# schematic_easyeda.net
KiCad netlist of a schematic drawn in EasyEDA
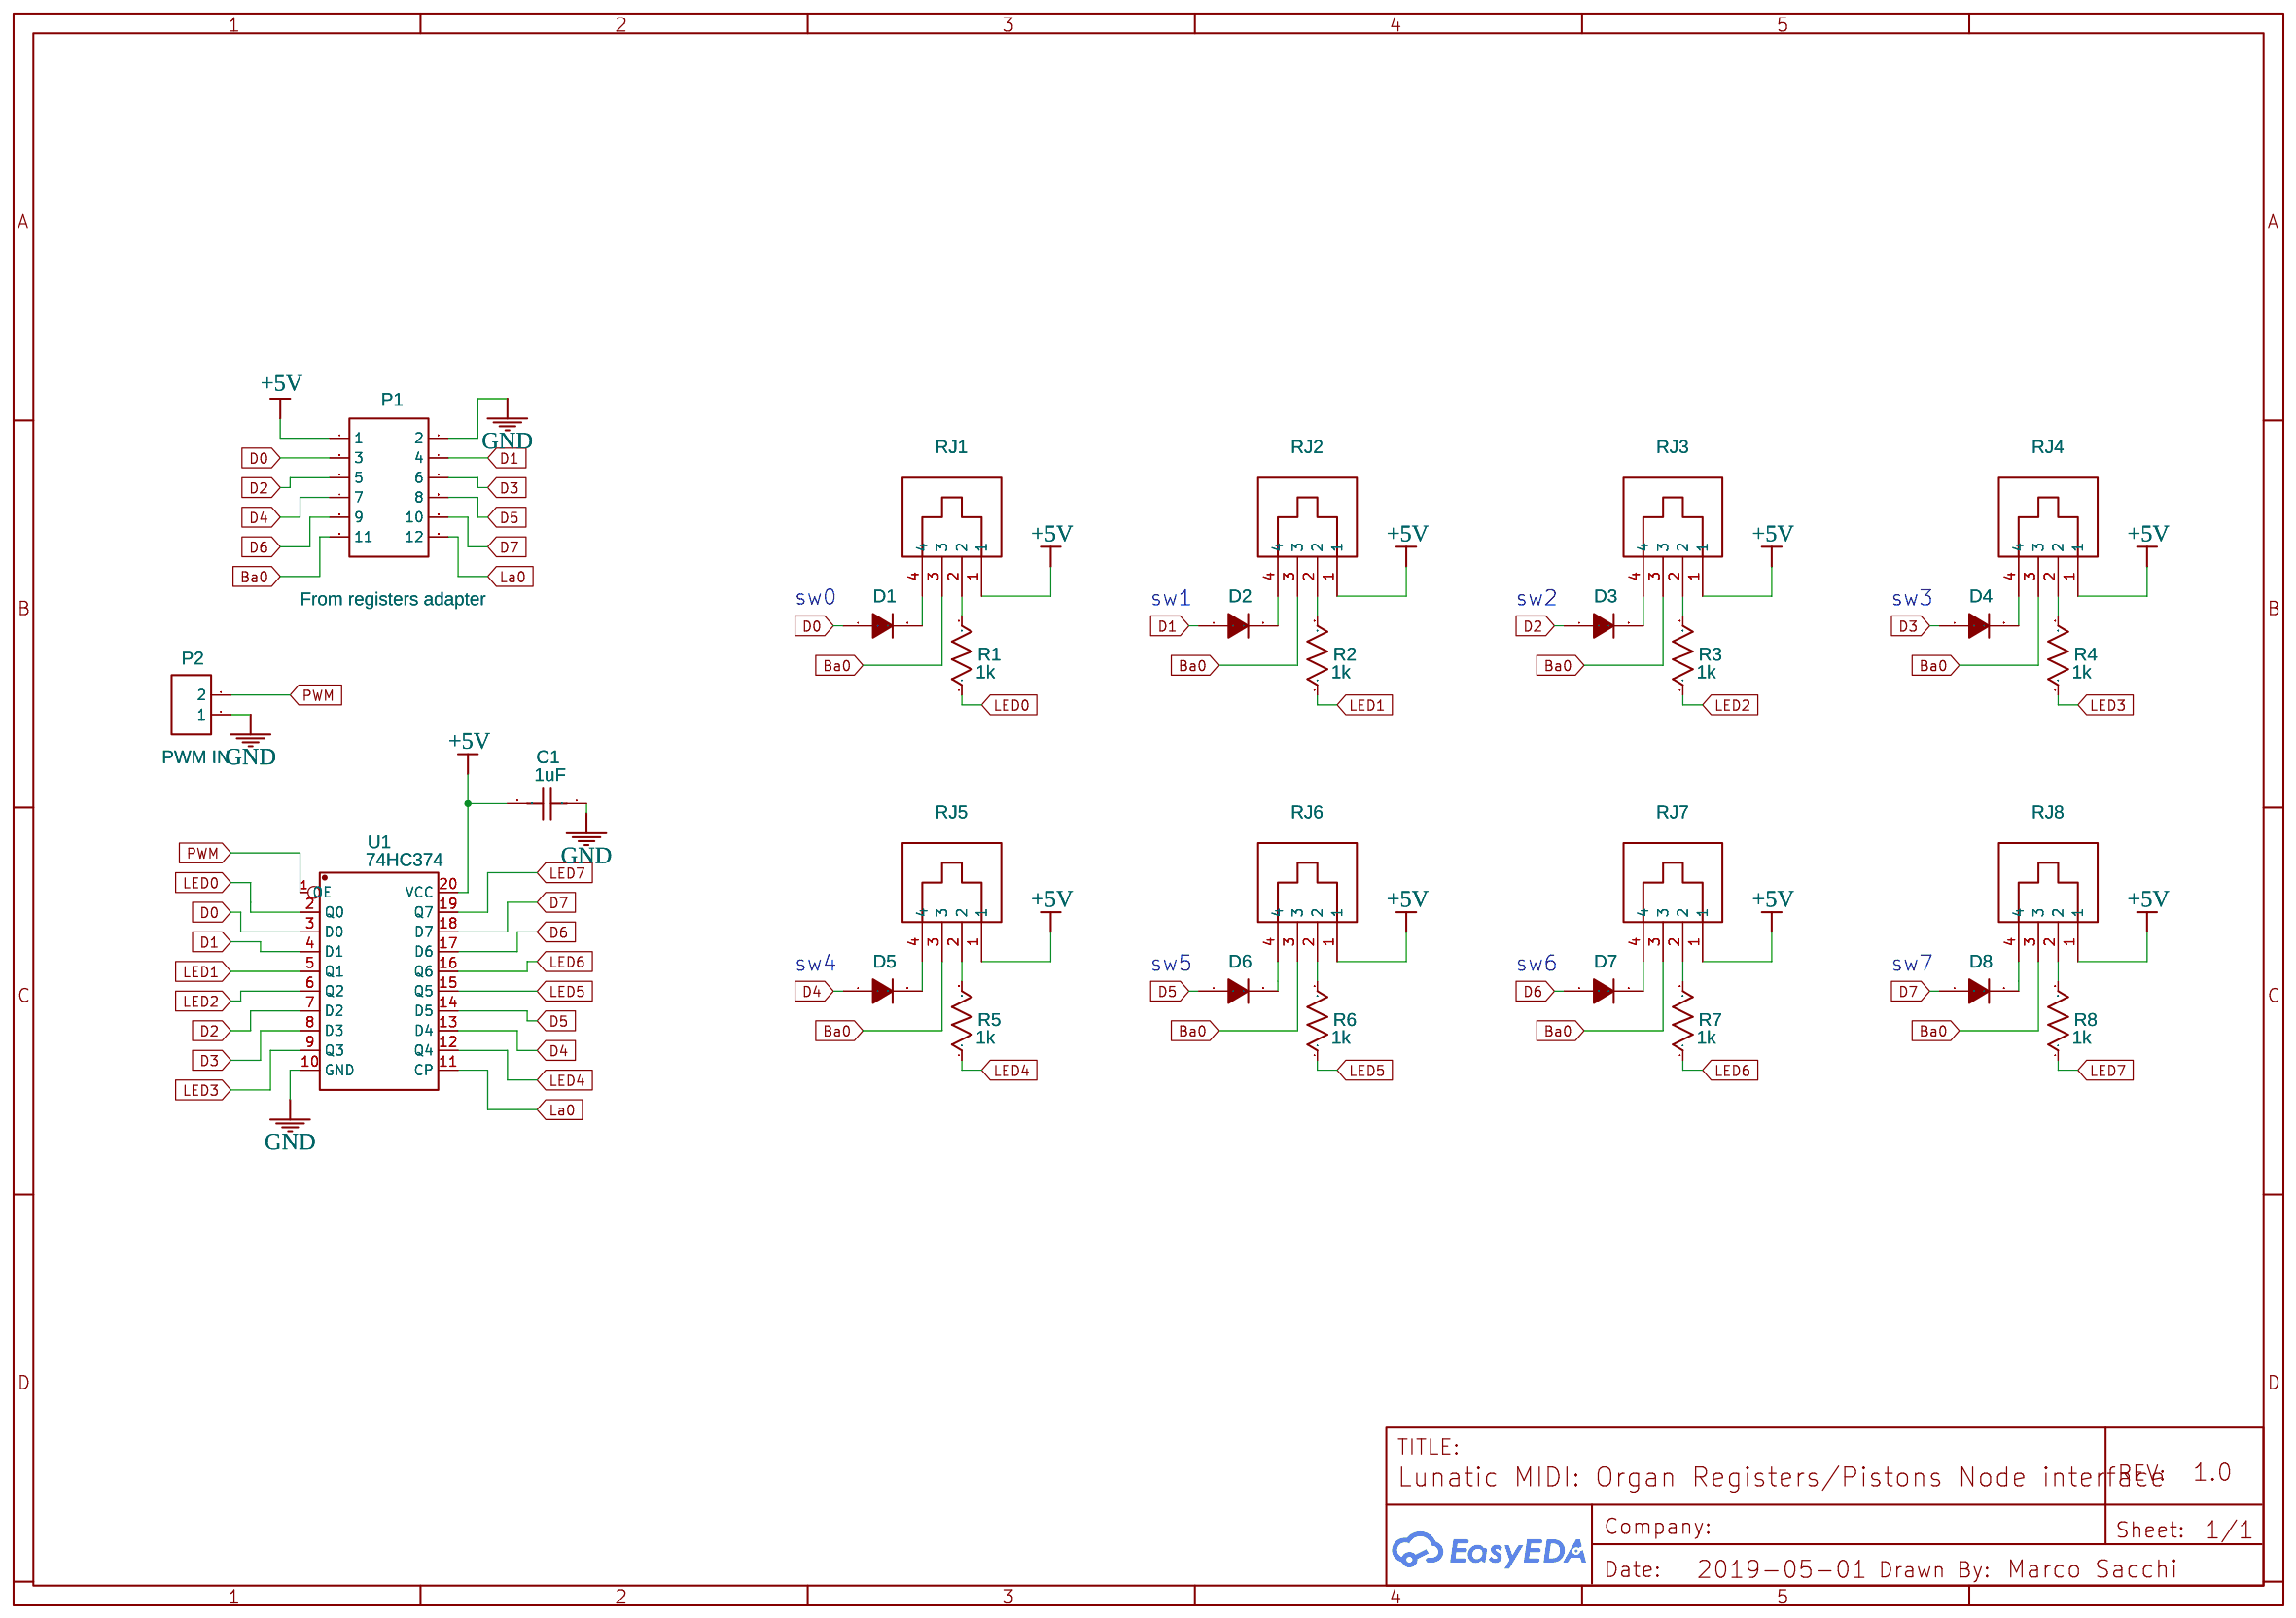
[diagram p0: schematic sheet]

(export (version "E")
  (design (tool "Eeschema 10.0.6"))
  (components
    (comp (ref "C1")
      (value "1uF")
      (fields (field (name "BOM_Manufacturer Part") "?"))
      (libsource (lib "") (part "Cap_RAD-0.1_US"))
    )
    (comp (ref "D1")
      (value "1N4148")
      (fields (field (name "BOM_Supplier Part") "C85057"))
      (libsource (lib "") (part "Unknown_440_310"))
    )
    (comp (ref "D2")
      (value "1N4148")
      (fields (field (name "BOM_Supplier Part") "C85057"))
      (libsource (lib "") (part "Unknown_620_310"))
    )
    (comp (ref "D3")
      (value "1N4148")
      (fields (field (name "BOM_Supplier Part") "C85057"))
      (libsource (lib "") (part "Unknown_805_310"))
    )
    (comp (ref "D4")
      (value "1N4148")
      (fields (field (name "BOM_Supplier Part") "C85057"))
      (libsource (lib "") (part "Unknown_995_310"))
    )
    (comp (ref "D5")
      (value "1N4148")
      (fields (field (name "BOM_Supplier Part") "C85057"))
      (libsource (lib "") (part "Unknown_440_495"))
    )
    (comp (ref "D6")
      (value "1N4148")
      (fields (field (name "BOM_Supplier Part") "C85057"))
      (libsource (lib "") (part "Unknown_620_495"))
    )
    (comp (ref "D7")
      (value "1N4148")
      (fields (field (name "BOM_Supplier Part") "C85057"))
      (libsource (lib "") (part "Unknown_805_495"))
    )
    (comp (ref "D8")
      (value "1N4148")
      (fields (field (name "BOM_Supplier Part") "C85057"))
      (libsource (lib "") (part "Unknown_995_495"))
    )
    (comp (ref "P1")
      (value "From registers adapter")
      (fields (field (name "BOM_Manufacturer Part") "?") (field (name "BOM_Supplier Part") "C66689"))
      (libsource (lib "") (part "Unknown_190_240"))
    )
    (comp (ref "P2")
      (value "PWM IN")
      (fields
        (field (name "BOM_Manufacturer Part") "2.54-1*2PFemale")
        (field (name "BOM_Supplier Part") "C49661")
      )
      (libsource (lib "") (part "Unknown_95_350"))
    )
    (comp (ref "R1")
      (value "1k")
      (fields (field (name "BOM_Manufacturer Part") "?"))
      (libsource (lib "") (part "Res_AXIAL-0.3(1/8W)_US"))
    )
    (comp (ref "R2")
      (value "1k")
      (fields (field (name "BOM_Manufacturer Part") "?"))
      (libsource (lib "") (part "Res_AXIAL-0.3(1/8W)_US"))
    )
    (comp (ref "R3")
      (value "1k")
      (fields (field (name "BOM_Manufacturer Part") "?"))
      (libsource (lib "") (part "Res_AXIAL-0.3(1/8W)_US"))
    )
    (comp (ref "R4")
      (value "1k")
      (fields (field (name "BOM_Manufacturer Part") "?"))
      (libsource (lib "") (part "Res_AXIAL-0.3(1/8W)_US"))
    )
    (comp (ref "R5")
      (value "1k")
      (fields (field (name "BOM_Manufacturer Part") "?"))
      (libsource (lib "") (part "Res_AXIAL-0.3(1/8W)_US"))
    )
    (comp (ref "R6")
      (value "1k")
      (fields (field (name "BOM_Manufacturer Part") "?"))
      (libsource (lib "") (part "Res_AXIAL-0.3(1/8W)_US"))
    )
    (comp (ref "R7")
      (value "1k")
      (fields (field (name "BOM_Manufacturer Part") "?"))
      (libsource (lib "") (part "Res_AXIAL-0.3(1/8W)_US"))
    )
    (comp (ref "R8")
      (value "1k")
      (fields (field (name "BOM_Manufacturer Part") "?"))
      (libsource (lib "") (part "Res_AXIAL-0.3(1/8W)_US"))
    )
    (comp (ref "RJ1")
      (value "RJ22-4P4C-90")
      (fields
        (field (name "BOM_Manufacturer Part") "1-1705949-1")
        (field (name "BOM_Supplier Part") "615-4232")
      )
      (libsource (lib "") (part "Unknown_475_265"))
    )
    (comp (ref "RJ2")
      (value "RJ22-4P4C-90")
      (fields
        (field (name "BOM_Manufacturer Part") "1-1705949-1")
        (field (name "BOM_Supplier Part") "615-4232")
      )
      (libsource (lib "") (part "Unknown_655_265"))
    )
    (comp (ref "RJ3")
      (value "RJ22-4P4C-90")
      (fields
        (field (name "BOM_Manufacturer Part") "1-1705949-1")
        (field (name "BOM_Supplier Part") "615-4232")
      )
      (libsource (lib "") (part "Unknown_840_265"))
    )
    (comp (ref "RJ4")
      (value "RJ22-4P4C-90")
      (fields
        (field (name "BOM_Manufacturer Part") "1-1705949-1")
        (field (name "BOM_Supplier Part") "615-4232")
      )
      (libsource (lib "") (part "Unknown_1030_265"))
    )
    (comp (ref "RJ5")
      (value "RJ22-4P4C-90")
      (fields
        (field (name "BOM_Manufacturer Part") "1-1705949-1")
        (field (name "BOM_Supplier Part") "615-4232")
      )
      (libsource (lib "") (part "Unknown_475_450"))
    )
    (comp (ref "RJ6")
      (value "RJ22-4P4C-90")
      (fields
        (field (name "BOM_Manufacturer Part") "1-1705949-1")
        (field (name "BOM_Supplier Part") "615-4232")
      )
      (libsource (lib "") (part "Unknown_655_450"))
    )
    (comp (ref "RJ7")
      (value "RJ22-4P4C-90")
      (fields
        (field (name "BOM_Manufacturer Part") "1-1705949-1")
        (field (name "BOM_Supplier Part") "615-4232")
      )
      (libsource (lib "") (part "Unknown_840_450"))
    )
    (comp (ref "RJ8")
      (value "RJ22-4P4C-90")
      (fields
        (field (name "BOM_Manufacturer Part") "1-1705949-1")
        (field (name "BOM_Supplier Part") "615-4232")
      )
      (libsource (lib "") (part "Unknown_1030_450"))
    )
    (comp (ref "U1")
      (value "74HC374")
      (fields (field (name "BOM_Supplier Part") "CD54"))
      (libsource (lib "") (part "Unknown_185_490"))
    )
  )
  (nets
    (net (code "1") (name "+5V") (class "Default")
      (node (ref "C1") (pin "2") (pinfunction "2_2") (pintype "unspecified"))
      (node (ref "P1") (pin "1") (pinfunction "1_1") (pintype "input"))
      (node (ref "RJ1") (pin "1") (pinfunction "1_1") (pintype "unspecified"))
      (node (ref "RJ2") (pin "1") (pinfunction "1_1") (pintype "unspecified"))
      (node (ref "RJ3") (pin "1") (pinfunction "1_1") (pintype "unspecified"))
      (node (ref "RJ4") (pin "1") (pinfunction "1_1") (pintype "unspecified"))
      (node (ref "RJ5") (pin "1") (pinfunction "1_1") (pintype "unspecified"))
      (node (ref "RJ6") (pin "1") (pinfunction "1_1") (pintype "unspecified"))
      (node (ref "RJ7") (pin "1") (pinfunction "1_1") (pintype "unspecified"))
      (node (ref "RJ8") (pin "1") (pinfunction "1_1") (pintype "unspecified"))
      (node (ref "U1") (pin "20") (pinfunction "VCC_20") (pintype "unspecified"))
    )
    (net (code "2") (name "Ba0") (class "Default")
      (node (ref "P1") (pin "11") (pinfunction "11_11") (pintype "input"))
      (node (ref "RJ1") (pin "3") (pinfunction "3_3") (pintype "unspecified"))
      (node (ref "RJ2") (pin "3") (pinfunction "3_3") (pintype "unspecified"))
      (node (ref "RJ3") (pin "3") (pinfunction "3_3") (pintype "unspecified"))
      (node (ref "RJ4") (pin "3") (pinfunction "3_3") (pintype "unspecified"))
      (node (ref "RJ5") (pin "3") (pinfunction "3_3") (pintype "unspecified"))
      (node (ref "RJ6") (pin "3") (pinfunction "3_3") (pintype "unspecified"))
      (node (ref "RJ7") (pin "3") (pinfunction "3_3") (pintype "unspecified"))
      (node (ref "RJ8") (pin "3") (pinfunction "3_3") (pintype "unspecified"))
    )
    (net (code "3") (name "D0") (class "Default")
      (node (ref "D1") (pin "1") (pinfunction "A_1") (pintype "unspecified"))
      (node (ref "P1") (pin "3") (pinfunction "3_3") (pintype "input"))
      (node (ref "U1") (pin "3") (pinfunction "D0_3") (pintype "unspecified"))
    )
    (net (code "4") (name "D1") (class "Default")
      (node (ref "D2") (pin "1") (pinfunction "A_1") (pintype "unspecified"))
      (node (ref "P1") (pin "4") (pinfunction "4_4") (pintype "input"))
      (node (ref "U1") (pin "4") (pinfunction "D1_4") (pintype "unspecified"))
    )
    (net (code "5") (name "D2") (class "Default")
      (node (ref "D3") (pin "1") (pinfunction "A_1") (pintype "unspecified"))
      (node (ref "P1") (pin "5") (pinfunction "5_5") (pintype "input"))
      (node (ref "U1") (pin "7") (pinfunction "D2_7") (pintype "unspecified"))
    )
    (net (code "6") (name "D3") (class "Default")
      (node (ref "D4") (pin "1") (pinfunction "A_1") (pintype "unspecified"))
      (node (ref "P1") (pin "6") (pinfunction "6_6") (pintype "input"))
      (node (ref "U1") (pin "8") (pinfunction "D3_8") (pintype "unspecified"))
    )
    (net (code "7") (name "D4") (class "Default")
      (node (ref "D5") (pin "1") (pinfunction "A_1") (pintype "unspecified"))
      (node (ref "P1") (pin "7") (pinfunction "7_7") (pintype "input"))
      (node (ref "U1") (pin "13") (pinfunction "D4_13") (pintype "unspecified"))
    )
    (net (code "8") (name "D5") (class "Default")
      (node (ref "D6") (pin "1") (pinfunction "A_1") (pintype "unspecified"))
      (node (ref "P1") (pin "8") (pinfunction "8_8") (pintype "input"))
      (node (ref "U1") (pin "14") (pinfunction "D5_14") (pintype "unspecified"))
    )
    (net (code "9") (name "D6") (class "Default")
      (node (ref "D7") (pin "1") (pinfunction "A_1") (pintype "unspecified"))
      (node (ref "P1") (pin "9") (pinfunction "9_9") (pintype "input"))
      (node (ref "U1") (pin "17") (pinfunction "D6_17") (pintype "unspecified"))
    )
    (net (code "10") (name "D7") (class "Default")
      (node (ref "D8") (pin "1") (pinfunction "A_1") (pintype "unspecified"))
      (node (ref "P1") (pin "10") (pinfunction "10_10") (pintype "input"))
      (node (ref "U1") (pin "18") (pinfunction "D7_18") (pintype "unspecified"))
    )
    (net (code "11") (name "GND") (class "Default")
      (node (ref "C1") (pin "1") (pinfunction "1_1") (pintype "unspecified"))
      (node (ref "P1") (pin "2") (pinfunction "2_2") (pintype "input"))
      (node (ref "P2") (pin "1") (pinfunction "1_1") (pintype "input"))
      (node (ref "U1") (pin "10") (pinfunction "GND_10") (pintype "unspecified"))
    )
    (net (code "12") (name "LED0") (class "Default")
      (node (ref "R1") (pin "1") (pinfunction "1_1") (pintype "unspecified"))
      (node (ref "U1") (pin "2") (pinfunction "Q0_2") (pintype "unspecified"))
    )
    (net (code "13") (name "LED1") (class "Default")
      (node (ref "R2") (pin "1") (pinfunction "1_1") (pintype "unspecified"))
      (node (ref "U1") (pin "5") (pinfunction "Q1_5") (pintype "unspecified"))
    )
    (net (code "14") (name "LED2") (class "Default")
      (node (ref "R3") (pin "1") (pinfunction "1_1") (pintype "unspecified"))
      (node (ref "U1") (pin "6") (pinfunction "Q2_6") (pintype "unspecified"))
    )
    (net (code "15") (name "LED3") (class "Default")
      (node (ref "R4") (pin "1") (pinfunction "1_1") (pintype "unspecified"))
      (node (ref "U1") (pin "9") (pinfunction "Q3_9") (pintype "unspecified"))
    )
    (net (code "16") (name "LED4") (class "Default")
      (node (ref "R5") (pin "1") (pinfunction "1_1") (pintype "unspecified"))
      (node (ref "U1") (pin "12") (pinfunction "Q4_12") (pintype "unspecified"))
    )
    (net (code "17") (name "LED5") (class "Default")
      (node (ref "R6") (pin "1") (pinfunction "1_1") (pintype "unspecified"))
      (node (ref "U1") (pin "15") (pinfunction "Q5_15") (pintype "unspecified"))
    )
    (net (code "18") (name "LED6") (class "Default")
      (node (ref "R7") (pin "1") (pinfunction "1_1") (pintype "unspecified"))
      (node (ref "U1") (pin "16") (pinfunction "Q6_16") (pintype "unspecified"))
    )
    (net (code "19") (name "LED7") (class "Default")
      (node (ref "R8") (pin "1") (pinfunction "1_1") (pintype "unspecified"))
      (node (ref "U1") (pin "19") (pinfunction "Q7_19") (pintype "unspecified"))
    )
    (net (code "20") (name "La0") (class "Default")
      (node (ref "P1") (pin "12") (pinfunction "12_12") (pintype "input"))
      (node (ref "U1") (pin "11") (pinfunction "CP_11") (pintype "unspecified"))
    )
    (net (code "21") (name "Net-(D1-K)") (class "Default")
      (node (ref "D1") (pin "2") (pinfunction "K_2") (pintype "unspecified"))
      (node (ref "RJ1") (pin "4") (pinfunction "4_4") (pintype "unspecified"))
    )
    (net (code "22") (name "Net-(D2-K)") (class "Default")
      (node (ref "D2") (pin "2") (pinfunction "K_2") (pintype "unspecified"))
      (node (ref "RJ2") (pin "4") (pinfunction "4_4") (pintype "unspecified"))
    )
    (net (code "23") (name "Net-(D3-K)") (class "Default")
      (node (ref "D3") (pin "2") (pinfunction "K_2") (pintype "unspecified"))
      (node (ref "RJ3") (pin "4") (pinfunction "4_4") (pintype "unspecified"))
    )
    (net (code "24") (name "Net-(D4-K)") (class "Default")
      (node (ref "D4") (pin "2") (pinfunction "K_2") (pintype "unspecified"))
      (node (ref "RJ4") (pin "4") (pinfunction "4_4") (pintype "unspecified"))
    )
    (net (code "25") (name "Net-(D5-K)") (class "Default")
      (node (ref "D5") (pin "2") (pinfunction "K_2") (pintype "unspecified"))
      (node (ref "RJ5") (pin "4") (pinfunction "4_4") (pintype "unspecified"))
    )
    (net (code "26") (name "Net-(D6-K)") (class "Default")
      (node (ref "D6") (pin "2") (pinfunction "K_2") (pintype "unspecified"))
      (node (ref "RJ6") (pin "4") (pinfunction "4_4") (pintype "unspecified"))
    )
    (net (code "27") (name "Net-(D7-K)") (class "Default")
      (node (ref "D7") (pin "2") (pinfunction "K_2") (pintype "unspecified"))
      (node (ref "RJ7") (pin "4") (pinfunction "4_4") (pintype "unspecified"))
    )
    (net (code "28") (name "Net-(D8-K)") (class "Default")
      (node (ref "D8") (pin "2") (pinfunction "K_2") (pintype "unspecified"))
      (node (ref "RJ8") (pin "4") (pinfunction "4_4") (pintype "unspecified"))
    )
    (net (code "29") (name "Net-(R1-Pad2)") (class "Default")
      (node (ref "R1") (pin "2") (pinfunction "2_2") (pintype "unspecified"))
      (node (ref "RJ1") (pin "2") (pinfunction "2_2") (pintype "unspecified"))
    )
    (net (code "30") (name "Net-(R2-Pad2)") (class "Default")
      (node (ref "R2") (pin "2") (pinfunction "2_2") (pintype "unspecified"))
      (node (ref "RJ2") (pin "2") (pinfunction "2_2") (pintype "unspecified"))
    )
    (net (code "31") (name "Net-(R3-Pad2)") (class "Default")
      (node (ref "R3") (pin "2") (pinfunction "2_2") (pintype "unspecified"))
      (node (ref "RJ3") (pin "2") (pinfunction "2_2") (pintype "unspecified"))
    )
    (net (code "32") (name "Net-(R4-Pad2)") (class "Default")
      (node (ref "R4") (pin "2") (pinfunction "2_2") (pintype "unspecified"))
      (node (ref "RJ4") (pin "2") (pinfunction "2_2") (pintype "unspecified"))
    )
    (net (code "33") (name "Net-(R5-Pad2)") (class "Default")
      (node (ref "R5") (pin "2") (pinfunction "2_2") (pintype "unspecified"))
      (node (ref "RJ5") (pin "2") (pinfunction "2_2") (pintype "unspecified"))
    )
    (net (code "34") (name "Net-(R6-Pad2)") (class "Default")
      (node (ref "R6") (pin "2") (pinfunction "2_2") (pintype "unspecified"))
      (node (ref "RJ6") (pin "2") (pinfunction "2_2") (pintype "unspecified"))
    )
    (net (code "35") (name "Net-(R7-Pad2)") (class "Default")
      (node (ref "R7") (pin "2") (pinfunction "2_2") (pintype "unspecified"))
      (node (ref "RJ7") (pin "2") (pinfunction "2_2") (pintype "unspecified"))
    )
    (net (code "36") (name "Net-(R8-Pad2)") (class "Default")
      (node (ref "R8") (pin "2") (pinfunction "2_2") (pintype "unspecified"))
      (node (ref "RJ8") (pin "2") (pinfunction "2_2") (pintype "unspecified"))
    )
    (net (code "37") (name "PWM") (class "Default")
      (node (ref "P2") (pin "2") (pinfunction "2_2") (pintype "input"))
      (node (ref "U1") (pin "1") (pinfunction "OE_1") (pintype "unspecified"))
    )
  )
)
